# Transmitter_Suface.net
KiCad netlist of a schematic drawn in Altium Designer
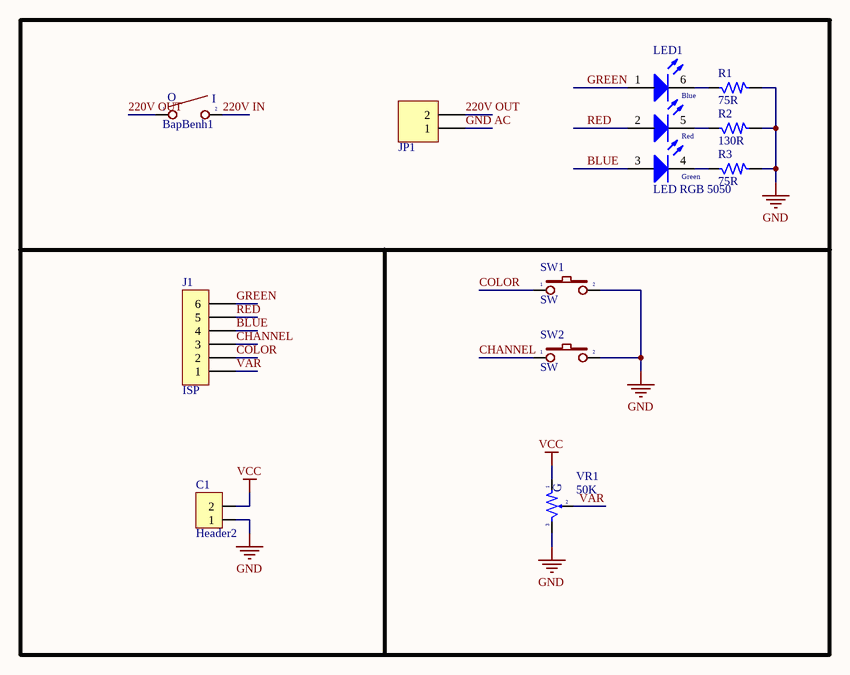
[diagram p0: Transmitter Suface.SchDoc]

(export (version "E")
  (design (tool "Eeschema 10.0.6"))
  (components
    (comp (ref "BapBenh1")
      (value "BapBenh")
      (footprint "HueNguyenLib:CONG TAC")
      (libsource (lib "Thu Vien Chuan") (part "BapBenh"))
    )
    (comp (ref "C1")
      (value "Header2")
      (footprint "HDR2")
      (description "Header IDC, 2 x 1 Pin Vertical 2.54mm Pitch (Non-Boxed, Male)")
      (fields
        (field (name "MANUFACTURER") "Würth Elektronik eiSos GmbH")
        (field (name "PARTNO") "613002143121")
        (field (name "CREATED BY") "Karrer Zheng")
      )
      (libsource (lib "Thu Vien Chuan") (part "Header2"))
    )
    (comp (ref "J1")
      (value "ISP")
      (footprint "Thu Vien Chuan :Header6")
      (description "JUMP DON DUC 2.54")
      (libsource (lib "Thu Vien Chuan") (part "JUMP 6"))
    )
    (comp (ref "JP1")
      (value "Header 2_1")
      (footprint "HED2")
      (description "Header, 2-Pin")
      (fields (field (name "MANUFACTURER") "Generic Components"))
      (libsource (lib "Thu Vien Chuan") (part "Header 2_1"))
    )
    (comp (ref "LED1")
      (value "LED RGB 5050")
      (footprint "LED RGB 5050")
      (fields
        (field (name "PARTNO") "150141M173100")
        (field (name "MANUFACTURER") "Würth Elektronik eiSos GmbH")
        (field (name "CREATED BY") "Christin Otto")
      )
      (libsource (lib "Thu Vien Chuan") (part "LED RGB 5050"))
    )
    (comp (ref "R1")
      (value "75R")
      (footprint "Thu Vien Chuan :RES-SMD-0805")
      (description "Tro 1/4W")
      (libsource (lib "Thu Vien Chuan") (part "RES 1/4W"))
    )
    (comp (ref "R2")
      (value "130R")
      (footprint "Thu Vien Chuan :RES-SMD-0805")
      (description "Tro 1/4W")
      (libsource (lib "Thu Vien Chuan") (part "RES 1/4W"))
    )
    (comp (ref "R3")
      (value "75R")
      (footprint "Thu Vien Chuan :RES-SMD-0805")
      (description "Tro 1/4W")
      (libsource (lib "Thu Vien Chuan") (part "RES 1/4W"))
    )
    (comp (ref "SW1")
      (value "SW")
      (footprint "SW2")
      (description "Switch button 2 pin")
      (libsource (lib "Thu Vien Chuan") (part "SW2"))
    )
    (comp (ref "SW2")
      (value "SW")
      (footprint "SW2")
      (description "Switch button 2 pin")
      (libsource (lib "Thu Vien Chuan") (part "SW2"))
    )
    (comp (ref "VR1")
      (value "50K")
      (footprint "Thu Vien Chuan :VR-S1 - CONG")
      (description "Var Resistor")
      (libsource (lib "Thu Vien Chuan") (part "VR-S"))
    )
  )
  (nets
    (net (code "1") (name "/220V IN") (class "Default")
      (node (ref "BapBenh1") (pin "2") (pinfunction "2_2") (pintype "passive"))
    )
    (net (code "2") (name "/220V OUT") (class "Default")
      (node (ref "BapBenh1") (pin "1") (pinfunction "1_1") (pintype "passive"))
      (node (ref "JP1") (pin "2") (pinfunction "2_2") (pintype "passive"))
    )
    (net (code "3") (name "/BLUE") (class "Default")
      (node (ref "J1") (pin "4") (pinfunction "4_4") (pintype "passive"))
      (node (ref "LED1") (pin "3") (pintype "passive"))
    )
    (net (code "4") (name "/CHANNEL") (class "Default")
      (node (ref "J1") (pin "3") (pinfunction "3_3") (pintype "passive"))
      (node (ref "SW2") (pin "1") (pinfunction "1_1") (pintype "passive"))
    )
    (net (code "5") (name "/COLOR") (class "Default")
      (node (ref "J1") (pin "2") (pinfunction "2_2") (pintype "passive"))
      (node (ref "SW1") (pin "1") (pinfunction "1_1") (pintype "passive"))
    )
    (net (code "6") (name "/GND AC") (class "Default")
      (node (ref "JP1") (pin "1") (pinfunction "1_1") (pintype "passive"))
    )
    (net (code "7") (name "/GREEN") (class "Default")
      (node (ref "J1") (pin "6") (pinfunction "6_6") (pintype "passive"))
      (node (ref "LED1") (pin "1") (pintype "passive"))
    )
    (net (code "8") (name "/RED") (class "Default")
      (node (ref "J1") (pin "5") (pinfunction "5_5") (pintype "passive"))
      (node (ref "LED1") (pin "2") (pintype "passive"))
    )
    (net (code "9") (name "/VAR") (class "Default")
      (node (ref "J1") (pin "1") (pinfunction "1_1") (pintype "passive"))
      (node (ref "VR1") (pin "2") (pinfunction "2_2") (pintype "passive"))
    )
    (net (code "10") (name "GND") (class "Default")
      (node (ref "C1") (pin "1") (pinfunction "1_1") (pintype "passive"))
      (node (ref "R1") (pin "2") (pinfunction "2_2") (pintype "passive"))
      (node (ref "R2") (pin "2") (pinfunction "2_2") (pintype "passive"))
      (node (ref "R3") (pin "2") (pinfunction "2_2") (pintype "passive"))
      (node (ref "SW1") (pin "2") (pinfunction "2_2") (pintype "passive"))
      (node (ref "SW2") (pin "2") (pinfunction "2_2") (pintype "passive"))
      (node (ref "VR1") (pin "3") (pinfunction "3_3") (pintype "passive"))
    )
    (net (code "11") (name "Net-(LED1-Pad4)") (class "Default")
      (node (ref "LED1") (pin "4") (pintype "passive"))
      (node (ref "R3") (pin "1") (pinfunction "1_1") (pintype "passive"))
    )
    (net (code "12") (name "Net-(LED1-Pad5)") (class "Default")
      (node (ref "LED1") (pin "5") (pintype "passive"))
      (node (ref "R2") (pin "1") (pinfunction "1_1") (pintype "passive"))
    )
    (net (code "13") (name "Net-(LED1-Pad6)") (class "Default")
      (node (ref "LED1") (pin "6") (pintype "passive"))
      (node (ref "R1") (pin "1") (pinfunction "1_1") (pintype "passive"))
    )
    (net (code "14") (name "VCC") (class "Default")
      (node (ref "C1") (pin "2") (pinfunction "2_2") (pintype "passive"))
      (node (ref "VR1") (pin "1") (pinfunction "1_1") (pintype "passive"))
    )
  )
)
